# LoRaWan.net
KiCad netlist of a schematic drawn in Altium Designer
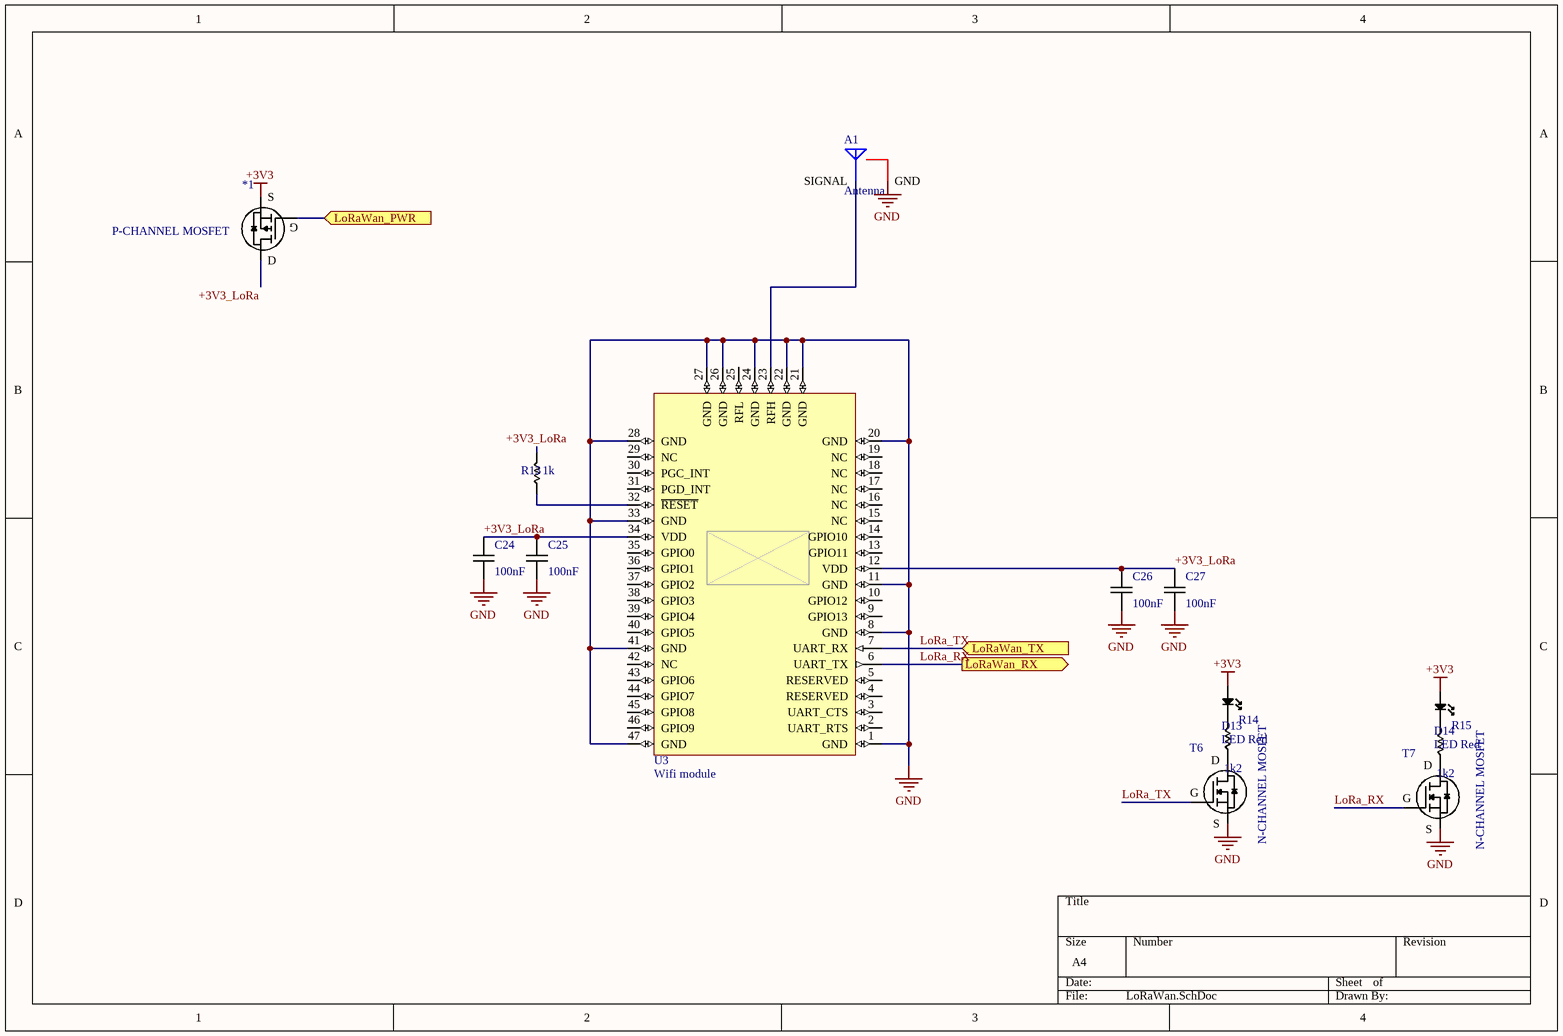
[diagram p0: LoRaWan.SchDoc]

(export (version "E")
  (design (tool "Eeschema 10.0.6"))
  (components
    (comp (ref "*1")
      (value "P-CHANNEL MOSFET")
      (footprint "P-CHANNEL MOSFET")
      (libsource (lib "Transistors") (part "P-CHANNEL MOSFET"))
    )
    (comp (ref "A1")
      (value "Antenna")
      (footprint "uFL SMD")
      (libsource (lib "altium-import") (part "root_0_uFL SMD_"))
    )
    (comp (ref "C24")
      (value "100nF")
      (footprint "C0603")
      (fields (field (name "Comment") "Capacitor 0603"))
      (libsource (lib "altium-import") (part "root_1_Capacitor 0603_"))
    )
    (comp (ref "C25")
      (value "100nF")
      (footprint "C0603")
      (fields (field (name "Comment") "Capacitor 0603"))
      (libsource (lib "altium-import") (part "root_1_Capacitor 0603_"))
    )
    (comp (ref "C26")
      (value "100nF")
      (footprint "C0603")
      (fields (field (name "Comment") "Capacitor 0603"))
      (libsource (lib "altium-import") (part "root_1_Capacitor 0603_"))
    )
    (comp (ref "C27")
      (value "100nF")
      (footprint "C0603")
      (fields (field (name "Comment") "Capacitor 0603"))
      (libsource (lib "altium-import") (part "root_1_Capacitor 0603_"))
    )
    (comp (ref "D13")
      (value "LED Red")
      (footprint "L0603 RED")
      (libsource (lib "Passive components") (part "LED 0603 Red"))
    )
    (comp (ref "D14")
      (value "LED Red")
      (footprint "L0603 RED")
      (libsource (lib "Passive components") (part "LED 0603 Red"))
    )
    (comp (ref "R13")
      (value "1k")
      (footprint "R0603")
      (fields (field (name "Comment") "Resistor 0603"))
      (libsource (lib "Passive components") (part "Resistor 0603"))
    )
    (comp (ref "R14")
      (value "1k2")
      (footprint "R0603")
      (fields (field (name "Comment") "Resistor 0603"))
      (libsource (lib "Passive components") (part "Resistor 0603"))
    )
    (comp (ref "R15")
      (value "1k2")
      (footprint "R0603")
      (fields (field (name "Comment") "Resistor 0603"))
      (libsource (lib "Passive components") (part "Resistor 0603"))
    )
    (comp (ref "T6")
      (value "N-CHANNEL MOSFET")
      (footprint "2N7002")
      (libsource (lib "Transistors") (part "2N7002"))
    )
    (comp (ref "T7")
      (value "N-CHANNEL MOSFET")
      (footprint "2N7002")
      (libsource (lib "Transistors") (part "2N7002"))
    )
    (comp (ref "U3")
      (value "Wifi module")
      (footprint "RN2483A")
      (description "RN2483A")
      (libsource (lib "altium-import") (part "root_0_LoRaWan module_"))
    )
  )
  (nets
    (net (code "1") (name "+3V3") (class "Default")
      (node (ref "*1") (pin "2") (pinfunction "S_2") (pintype "passive"))
      (node (ref "D13") (pin "1") (pinfunction "1_1") (pintype "passive"))
      (node (ref "D14") (pin "1") (pinfunction "1_1") (pintype "passive"))
    )
    (net (code "2") (name "/+3V3_LoRa") (class "Default")
      (node (ref "*1") (pin "3") (pinfunction "D_3") (pintype "passive"))
      (node (ref "C24") (pin "2") (pinfunction "2_2") (pintype "passive"))
      (node (ref "C25") (pin "2") (pinfunction "2_2") (pintype "passive"))
      (node (ref "C26") (pin "2") (pinfunction "2_2") (pintype "passive"))
      (node (ref "C27") (pin "2") (pinfunction "2_2") (pintype "passive"))
      (node (ref "R13") (pin "2") (pinfunction "2_2") (pintype "passive"))
      (node (ref "U3") (pin "12") (pinfunction "VDD_12") (pintype "bidirectional"))
      (node (ref "U3") (pin "34") (pinfunction "VDD_34") (pintype "bidirectional"))
    )
    (net (code "3") (name "/LoRaWan_PWR") (class "Default")
      (node (ref "*1") (pin "1") (pinfunction "G_1") (pintype "passive"))
    )
    (net (code "4") (name "/LoRa_RX") (class "Default")
      (node (ref "T7") (pin "1") (pinfunction "G_1") (pintype "passive"))
      (node (ref "U3") (pin "6") (pinfunction "UART_TX_6") (pintype "output"))
    )
    (net (code "5") (name "/LoRa_TX") (class "Default")
      (node (ref "T6") (pin "1") (pinfunction "G_1") (pintype "passive"))
      (node (ref "U3") (pin "7") (pinfunction "UART_RX_7") (pintype "input"))
    )
    (net (code "6") (name "GND") (class "Default")
      (node (ref "A1") (pin "2") (pinfunction "GND_2") (pintype "passive"))
      (node (ref "C24") (pin "1") (pinfunction "1_1") (pintype "passive"))
      (node (ref "C25") (pin "1") (pinfunction "1_1") (pintype "passive"))
      (node (ref "C26") (pin "1") (pinfunction "1_1") (pintype "passive"))
      (node (ref "C27") (pin "1") (pinfunction "1_1") (pintype "passive"))
      (node (ref "T6") (pin "2") (pinfunction "S_2") (pintype "passive"))
      (node (ref "T7") (pin "2") (pinfunction "S_2") (pintype "passive"))
      (node (ref "U3") (pin "1") (pinfunction "GND_1") (pintype "bidirectional"))
      (node (ref "U3") (pin "11") (pinfunction "GND_11") (pintype "bidirectional"))
      (node (ref "U3") (pin "20") (pinfunction "GND_20") (pintype "bidirectional"))
      (node (ref "U3") (pin "21") (pinfunction "GND_21") (pintype "bidirectional"))
      (node (ref "U3") (pin "22") (pinfunction "GND_22") (pintype "bidirectional"))
      (node (ref "U3") (pin "24") (pinfunction "GND_24") (pintype "bidirectional"))
      (node (ref "U3") (pin "26") (pinfunction "GND_26") (pintype "bidirectional"))
      (node (ref "U3") (pin "27") (pinfunction "GND_27") (pintype "bidirectional"))
      (node (ref "U3") (pin "28") (pinfunction "GND_28") (pintype "bidirectional"))
      (node (ref "U3") (pin "33") (pinfunction "GND_33") (pintype "bidirectional"))
      (node (ref "U3") (pin "41") (pinfunction "GND_41") (pintype "bidirectional"))
      (node (ref "U3") (pin "47") (pinfunction "GND_47") (pintype "bidirectional"))
      (node (ref "U3") (pin "8") (pinfunction "GND_8") (pintype "bidirectional"))
    )
    (net (code "7") (name "Net-(A1-SIGNAL)") (class "Default")
      (node (ref "A1") (pin "1") (pinfunction "SIGNAL_1") (pintype "passive"))
      (node (ref "U3") (pin "23") (pinfunction "RFH_23") (pintype "bidirectional"))
    )
    (net (code "8") (name "Net-(D13-Pad2)") (class "Default")
      (node (ref "D13") (pin "2") (pinfunction "2_2") (pintype "passive"))
      (node (ref "R14") (pin "2") (pinfunction "2_2") (pintype "passive"))
    )
    (net (code "9") (name "Net-(D14-Pad2)") (class "Default")
      (node (ref "D14") (pin "2") (pinfunction "2_2") (pintype "passive"))
      (node (ref "R15") (pin "2") (pinfunction "2_2") (pintype "passive"))
    )
    (net (code "10") (name "Net-(T6-D)") (class "Default")
      (node (ref "R14") (pin "1") (pinfunction "1_1") (pintype "passive"))
      (node (ref "T6") (pin "3") (pinfunction "D_3") (pintype "passive"))
    )
    (net (code "11") (name "Net-(T7-D)") (class "Default")
      (node (ref "R15") (pin "1") (pinfunction "1_1") (pintype "passive"))
      (node (ref "T7") (pin "3") (pinfunction "D_3") (pintype "passive"))
    )
    (net (code "12") (name "Net-(U3-~{RESET})") (class "Default")
      (node (ref "R13") (pin "1") (pinfunction "1_1") (pintype "passive"))
      (node (ref "U3") (pin "32") (pinfunction "~{RESET}_32") (pintype "bidirectional"))
    )
    (net (code "13") (name "unconnected-(U3-GPIO0-Pad35)") (class "Default")
      (node (ref "U3") (pin "35") (pinfunction "GPIO0_35") (pintype "bidirectional"))
    )
    (net (code "14") (name "unconnected-(U3-GPIO1-Pad36)") (class "Default")
      (node (ref "U3") (pin "36") (pinfunction "GPIO1_36") (pintype "bidirectional"))
    )
    (net (code "15") (name "unconnected-(U3-GPIO2-Pad37)") (class "Default")
      (node (ref "U3") (pin "37") (pinfunction "GPIO2_37") (pintype "bidirectional"))
    )
    (net (code "16") (name "unconnected-(U3-GPIO3-Pad38)") (class "Default")
      (node (ref "U3") (pin "38") (pinfunction "GPIO3_38") (pintype "bidirectional"))
    )
    (net (code "17") (name "unconnected-(U3-GPIO4-Pad39)") (class "Default")
      (node (ref "U3") (pin "39") (pinfunction "GPIO4_39") (pintype "bidirectional"))
    )
    (net (code "18") (name "unconnected-(U3-GPIO5-Pad40)") (class "Default")
      (node (ref "U3") (pin "40") (pinfunction "GPIO5_40") (pintype "bidirectional"))
    )
    (net (code "19") (name "unconnected-(U3-GPIO6-Pad43)") (class "Default")
      (node (ref "U3") (pin "43") (pinfunction "GPIO6_43") (pintype "bidirectional"))
    )
    (net (code "20") (name "unconnected-(U3-GPIO7-Pad44)") (class "Default")
      (node (ref "U3") (pin "44") (pinfunction "GPIO7_44") (pintype "bidirectional"))
    )
    (net (code "21") (name "unconnected-(U3-GPIO8-Pad45)") (class "Default")
      (node (ref "U3") (pin "45") (pinfunction "GPIO8_45") (pintype "bidirectional"))
    )
    (net (code "22") (name "unconnected-(U3-GPIO9-Pad46)") (class "Default")
      (node (ref "U3") (pin "46") (pinfunction "GPIO9_46") (pintype "bidirectional"))
    )
    (net (code "23") (name "unconnected-(U3-GPIO10-Pad14)") (class "Default")
      (node (ref "U3") (pin "14") (pinfunction "GPIO10_14") (pintype "bidirectional"))
    )
    (net (code "24") (name "unconnected-(U3-GPIO11-Pad13)") (class "Default")
      (node (ref "U3") (pin "13") (pinfunction "GPIO11_13") (pintype "bidirectional"))
    )
    (net (code "25") (name "unconnected-(U3-GPIO12-Pad10)") (class "Default")
      (node (ref "U3") (pin "10") (pinfunction "GPIO12_10") (pintype "bidirectional"))
    )
    (net (code "26") (name "unconnected-(U3-GPIO13-Pad9)") (class "Default")
      (node (ref "U3") (pin "9") (pinfunction "GPIO13_9") (pintype "bidirectional"))
    )
    (net (code "27") (name "unconnected-(U3-NC-Pad15)") (class "Default")
      (node (ref "U3") (pin "15") (pinfunction "NC_15") (pintype "bidirectional"))
    )
    (net (code "28") (name "unconnected-(U3-NC-Pad16)") (class "Default")
      (node (ref "U3") (pin "16") (pinfunction "NC_16") (pintype "bidirectional"))
    )
    (net (code "29") (name "unconnected-(U3-NC-Pad17)") (class "Default")
      (node (ref "U3") (pin "17") (pinfunction "NC_17") (pintype "bidirectional"))
    )
    (net (code "30") (name "unconnected-(U3-NC-Pad18)") (class "Default")
      (node (ref "U3") (pin "18") (pinfunction "NC_18") (pintype "bidirectional"))
    )
    (net (code "31") (name "unconnected-(U3-NC-Pad19)") (class "Default")
      (node (ref "U3") (pin "19") (pinfunction "NC_19") (pintype "bidirectional"))
    )
    (net (code "32") (name "unconnected-(U3-NC-Pad29)") (class "Default")
      (node (ref "U3") (pin "29") (pinfunction "NC_29") (pintype "bidirectional"))
    )
    (net (code "33") (name "unconnected-(U3-NC-Pad42)") (class "Default")
      (node (ref "U3") (pin "42") (pinfunction "NC_42") (pintype "bidirectional"))
    )
    (net (code "34") (name "unconnected-(U3-PGC_INT-Pad30)") (class "Default")
      (node (ref "U3") (pin "30") (pinfunction "PGC_INT_30") (pintype "bidirectional"))
    )
    (net (code "35") (name "unconnected-(U3-PGD_INT-Pad31)") (class "Default")
      (node (ref "U3") (pin "31") (pinfunction "PGD_INT_31") (pintype "bidirectional"))
    )
    (net (code "36") (name "unconnected-(U3-RESERVED-Pad4)") (class "Default")
      (node (ref "U3") (pin "4") (pinfunction "RESERVED_4") (pintype "bidirectional"))
    )
    (net (code "37") (name "unconnected-(U3-RESERVED-Pad5)") (class "Default")
      (node (ref "U3") (pin "5") (pinfunction "RESERVED_5") (pintype "bidirectional"))
    )
    (net (code "38") (name "unconnected-(U3-RFL-Pad25)") (class "Default")
      (node (ref "U3") (pin "25") (pinfunction "RFL_25") (pintype "bidirectional"))
    )
    (net (code "39") (name "unconnected-(U3-UART_CTS-Pad3)") (class "Default")
      (node (ref "U3") (pin "3") (pinfunction "UART_CTS_3") (pintype "bidirectional"))
    )
    (net (code "40") (name "unconnected-(U3-UART_RTS-Pad2)") (class "Default")
      (node (ref "U3") (pin "2") (pinfunction "UART_RTS_2") (pintype "bidirectional"))
    )
  )
)
